# 20260108.net
KiCad netlist of a schematic drawn in EasyEDA Pro
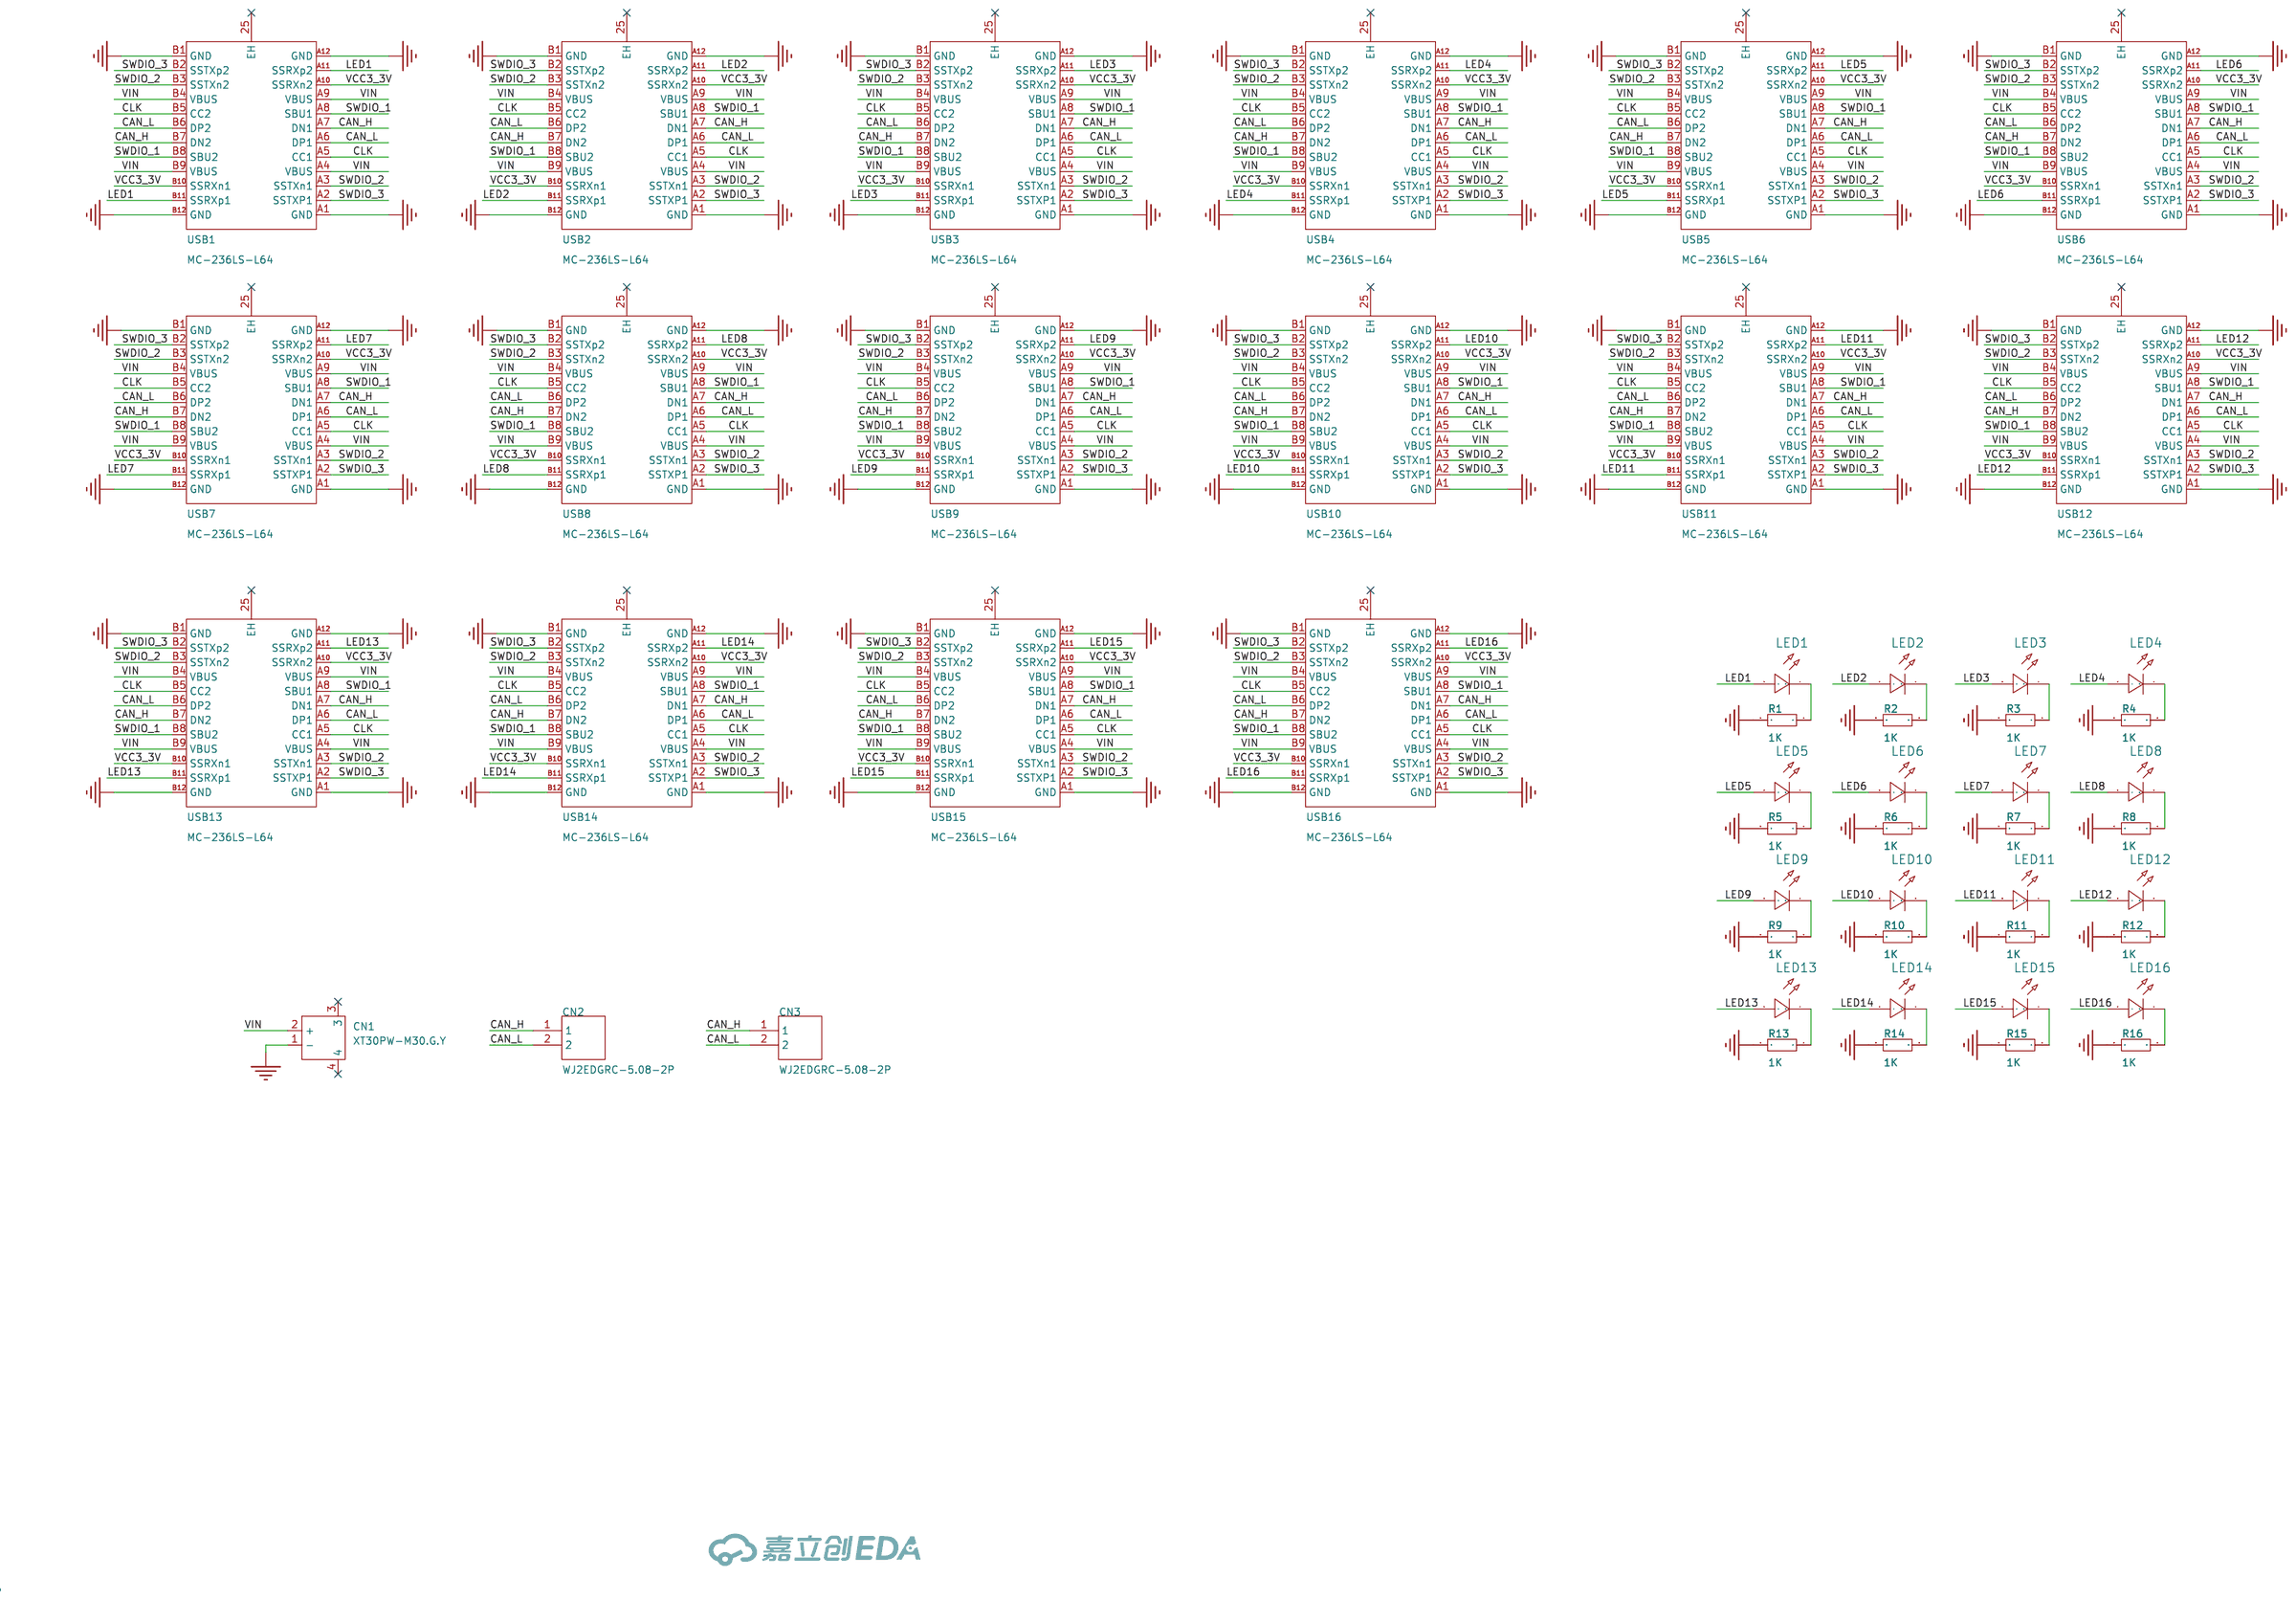
[diagram p0: schematic sheet]

(export (version "E")
  (design (tool "Eeschema 10.0.6"))
  (components
    (comp (ref "CN1")
      (value "XT30PW-M30.G.Y")
      (footprint "easyedapro:CONN-TH_XT30PW-M")
      (description "类别:-;类型1:-;")
      (fields (field (name "Manufacturer") "AMASS(艾迈斯)"))
      (libsource (lib "easyedapro") (part "XT30PW-M"))
    )
    (comp (ref "CN2")
      (value "WJ2EDGRC-5.08-2P")
      (footprint "easyedapro:CONN-TH_2P-P5.08_WJ2EDGRC-5.08-2P")
      (fields (field (name "Manufacturer") "KANGNEX(康奈克斯电气)"))
      (libsource (lib "easyedapro") (part "WJ2EDGRC-5.08-2P"))
    )
    (comp (ref "CN3")
      (value "WJ2EDGRC-5.08-2P")
      (footprint "easyedapro:CONN-TH_2P-P5.08_WJ2EDGRC-5.08-2P")
      (fields (field (name "Manufacturer") "KANGNEX(康奈克斯电气)"))
      (libsource (lib "easyedapro") (part "WJ2EDGRC-5.08-2P"))
    )
    (comp (ref "LED1")
      (value "~")
      (footprint "easyedapro:LED_0805")
      (libsource (lib "easyedapro") (part "LED_R"))
    )
    (comp (ref "LED2")
      (value "~")
      (footprint "easyedapro:LED_0805")
      (libsource (lib "easyedapro") (part "LED_R"))
    )
    (comp (ref "LED3")
      (value "~")
      (footprint "easyedapro:LED_0805")
      (libsource (lib "easyedapro") (part "LED_R"))
    )
    (comp (ref "LED4")
      (value "~")
      (footprint "easyedapro:LED_0805")
      (libsource (lib "easyedapro") (part "LED_R"))
    )
    (comp (ref "LED5")
      (value "~")
      (footprint "easyedapro:LED_0805")
      (libsource (lib "easyedapro") (part "LED_R"))
    )
    (comp (ref "LED6")
      (value "~")
      (footprint "easyedapro:LED_0805")
      (libsource (lib "easyedapro") (part "LED_R"))
    )
    (comp (ref "LED7")
      (value "~")
      (footprint "easyedapro:LED_0805")
      (libsource (lib "easyedapro") (part "LED_R"))
    )
    (comp (ref "LED8")
      (value "~")
      (footprint "easyedapro:LED_0805")
      (libsource (lib "easyedapro") (part "LED_R"))
    )
    (comp (ref "LED9")
      (value "~")
      (footprint "easyedapro:LED_0805")
      (libsource (lib "easyedapro") (part "LED_R"))
    )
    (comp (ref "LED10")
      (value "~")
      (footprint "easyedapro:LED_0805")
      (libsource (lib "easyedapro") (part "LED_R"))
    )
    (comp (ref "LED11")
      (value "~")
      (footprint "easyedapro:LED_0805")
      (libsource (lib "easyedapro") (part "LED_R"))
    )
    (comp (ref "LED12")
      (value "~")
      (footprint "easyedapro:LED_0805")
      (libsource (lib "easyedapro") (part "LED_R"))
    )
    (comp (ref "LED13")
      (value "~")
      (footprint "easyedapro:LED_0805")
      (libsource (lib "easyedapro") (part "LED_R"))
    )
    (comp (ref "LED14")
      (value "~")
      (footprint "easyedapro:LED_0805")
      (libsource (lib "easyedapro") (part "LED_R"))
    )
    (comp (ref "LED15")
      (value "~")
      (footprint "easyedapro:LED_0805")
      (libsource (lib "easyedapro") (part "LED_R"))
    )
    (comp (ref "LED16")
      (value "~")
      (footprint "easyedapro:LED_0805")
      (libsource (lib "easyedapro") (part "LED_R"))
    )
    (comp (ref "R1") (value "1K") (footprint "easyedapro:R0805") (libsource (lib "easyedapro") (part "电阻")))
    (comp (ref "R2") (value "1K") (footprint "easyedapro:R0805") (libsource (lib "easyedapro") (part "电阻")))
    (comp (ref "R3") (value "1K") (footprint "easyedapro:R0805") (libsource (lib "easyedapro") (part "电阻")))
    (comp (ref "R4") (value "1K") (footprint "easyedapro:R0805") (libsource (lib "easyedapro") (part "电阻")))
    (comp (ref "R5") (value "1K") (footprint "easyedapro:R0805") (libsource (lib "easyedapro") (part "电阻")))
    (comp (ref "R6") (value "1K") (footprint "easyedapro:R0805") (libsource (lib "easyedapro") (part "电阻")))
    (comp (ref "R7") (value "1K") (footprint "easyedapro:R0805") (libsource (lib "easyedapro") (part "电阻")))
    (comp (ref "R8") (value "1K") (footprint "easyedapro:R0805") (libsource (lib "easyedapro") (part "电阻")))
    (comp (ref "R9") (value "1K") (footprint "easyedapro:R0805") (libsource (lib "easyedapro") (part "电阻")))
    (comp (ref "R10") (value "1K") (footprint "easyedapro:R0805") (libsource (lib "easyedapro") (part "电阻")))
    (comp (ref "R11") (value "1K") (footprint "easyedapro:R0805") (libsource (lib "easyedapro") (part "电阻")))
    (comp (ref "R12") (value "1K") (footprint "easyedapro:R0805") (libsource (lib "easyedapro") (part "电阻")))
    (comp (ref "R13") (value "1K") (footprint "easyedapro:R0805") (libsource (lib "easyedapro") (part "电阻")))
    (comp (ref "R14") (value "1K") (footprint "easyedapro:R0805") (libsource (lib "easyedapro") (part "电阻")))
    (comp (ref "R15") (value "1K") (footprint "easyedapro:R0805") (libsource (lib "easyedapro") (part "电阻")))
    (comp (ref "R16") (value "1K") (footprint "easyedapro:R0805") (libsource (lib "easyedapro") (part "电阻")))
    (comp (ref "USB1")
      (value "MC-236LS-L64")
      (footprint "easyedapro:TYPE-C-USB-SMD_TYPE-C-31-M-06")
      (description "连接器类型:Type-C;协议标准:USB 3.1;公母:母;安装方式:立贴;触点数量:24P;端口数量:1;额定电流 - 电源:5A;工作温度:-25°C~+85°C;")
      (fields (field (name "Manufacturer") "HANBO(汉博)"))
      (libsource (lib "easyedapro") (part "MC-236LS-L64"))
    )
    (comp (ref "USB2")
      (value "MC-236LS-L64")
      (footprint "easyedapro:TYPE-C-USB-SMD_TYPE-C-31-M-06")
      (description "连接器类型:Type-C;协议标准:USB 3.1;公母:母;安装方式:立贴;触点数量:24P;端口数量:1;额定电流 - 电源:5A;工作温度:-25°C~+85°C;")
      (fields (field (name "Manufacturer") "HANBO(汉博)"))
      (libsource (lib "easyedapro") (part "MC-236LS-L64"))
    )
    (comp (ref "USB3")
      (value "MC-236LS-L64")
      (footprint "easyedapro:TYPE-C-USB-SMD_TYPE-C-31-M-06")
      (description "连接器类型:Type-C;协议标准:USB 3.1;公母:母;安装方式:立贴;触点数量:24P;端口数量:1;额定电流 - 电源:5A;工作温度:-25°C~+85°C;")
      (fields (field (name "Manufacturer") "HANBO(汉博)"))
      (libsource (lib "easyedapro") (part "MC-236LS-L64"))
    )
    (comp (ref "USB4")
      (value "MC-236LS-L64")
      (footprint "easyedapro:TYPE-C-USB-SMD_TYPE-C-31-M-06")
      (description "连接器类型:Type-C;协议标准:USB 3.1;公母:母;安装方式:立贴;触点数量:24P;端口数量:1;额定电流 - 电源:5A;工作温度:-25°C~+85°C;")
      (fields (field (name "Manufacturer") "HANBO(汉博)"))
      (libsource (lib "easyedapro") (part "MC-236LS-L64"))
    )
    (comp (ref "USB5")
      (value "MC-236LS-L64")
      (footprint "easyedapro:TYPE-C-USB-SMD_TYPE-C-31-M-06")
      (description "连接器类型:Type-C;协议标准:USB 3.1;公母:母;安装方式:立贴;触点数量:24P;端口数量:1;额定电流 - 电源:5A;工作温度:-25°C~+85°C;")
      (fields (field (name "Manufacturer") "HANBO(汉博)"))
      (libsource (lib "easyedapro") (part "MC-236LS-L64"))
    )
    (comp (ref "USB6")
      (value "MC-236LS-L64")
      (footprint "easyedapro:TYPE-C-USB-SMD_TYPE-C-31-M-06")
      (description "连接器类型:Type-C;协议标准:USB 3.1;公母:母;安装方式:立贴;触点数量:24P;端口数量:1;额定电流 - 电源:5A;工作温度:-25°C~+85°C;")
      (fields (field (name "Manufacturer") "HANBO(汉博)"))
      (libsource (lib "easyedapro") (part "MC-236LS-L64"))
    )
    (comp (ref "USB7")
      (value "MC-236LS-L64")
      (footprint "easyedapro:TYPE-C-USB-SMD_TYPE-C-31-M-06")
      (description "连接器类型:Type-C;协议标准:USB 3.1;公母:母;安装方式:立贴;触点数量:24P;端口数量:1;额定电流 - 电源:5A;工作温度:-25°C~+85°C;")
      (fields (field (name "Manufacturer") "HANBO(汉博)"))
      (libsource (lib "easyedapro") (part "MC-236LS-L64"))
    )
    (comp (ref "USB8")
      (value "MC-236LS-L64")
      (footprint "easyedapro:TYPE-C-USB-SMD_TYPE-C-31-M-06")
      (description "连接器类型:Type-C;协议标准:USB 3.1;公母:母;安装方式:立贴;触点数量:24P;端口数量:1;额定电流 - 电源:5A;工作温度:-25°C~+85°C;")
      (fields (field (name "Manufacturer") "HANBO(汉博)"))
      (libsource (lib "easyedapro") (part "MC-236LS-L64"))
    )
    (comp (ref "USB9")
      (value "MC-236LS-L64")
      (footprint "easyedapro:TYPE-C-USB-SMD_TYPE-C-31-M-06")
      (description "连接器类型:Type-C;协议标准:USB 3.1;公母:母;安装方式:立贴;触点数量:24P;端口数量:1;额定电流 - 电源:5A;工作温度:-25°C~+85°C;")
      (fields (field (name "Manufacturer") "HANBO(汉博)"))
      (libsource (lib "easyedapro") (part "MC-236LS-L64"))
    )
    (comp (ref "USB10")
      (value "MC-236LS-L64")
      (footprint "easyedapro:TYPE-C-USB-SMD_TYPE-C-31-M-06")
      (description "连接器类型:Type-C;协议标准:USB 3.1;公母:母;安装方式:立贴;触点数量:24P;端口数量:1;额定电流 - 电源:5A;工作温度:-25°C~+85°C;")
      (fields (field (name "Manufacturer") "HANBO(汉博)"))
      (libsource (lib "easyedapro") (part "MC-236LS-L64"))
    )
    (comp (ref "USB11")
      (value "MC-236LS-L64")
      (footprint "easyedapro:TYPE-C-USB-SMD_TYPE-C-31-M-06")
      (description "连接器类型:Type-C;协议标准:USB 3.1;公母:母;安装方式:立贴;触点数量:24P;端口数量:1;额定电流 - 电源:5A;工作温度:-25°C~+85°C;")
      (fields (field (name "Manufacturer") "HANBO(汉博)"))
      (libsource (lib "easyedapro") (part "MC-236LS-L64"))
    )
    (comp (ref "USB12")
      (value "MC-236LS-L64")
      (footprint "easyedapro:TYPE-C-USB-SMD_TYPE-C-31-M-06")
      (description "连接器类型:Type-C;协议标准:USB 3.1;公母:母;安装方式:立贴;触点数量:24P;端口数量:1;额定电流 - 电源:5A;工作温度:-25°C~+85°C;")
      (fields (field (name "Manufacturer") "HANBO(汉博)"))
      (libsource (lib "easyedapro") (part "MC-236LS-L64"))
    )
    (comp (ref "USB13")
      (value "MC-236LS-L64")
      (footprint "easyedapro:TYPE-C-USB-SMD_TYPE-C-31-M-06")
      (description "连接器类型:Type-C;协议标准:USB 3.1;公母:母;安装方式:立贴;触点数量:24P;端口数量:1;额定电流 - 电源:5A;工作温度:-25°C~+85°C;")
      (fields (field (name "Manufacturer") "HANBO(汉博)"))
      (libsource (lib "easyedapro") (part "MC-236LS-L64"))
    )
    (comp (ref "USB14")
      (value "MC-236LS-L64")
      (footprint "easyedapro:TYPE-C-USB-SMD_TYPE-C-31-M-06")
      (description "连接器类型:Type-C;协议标准:USB 3.1;公母:母;安装方式:立贴;触点数量:24P;端口数量:1;额定电流 - 电源:5A;工作温度:-25°C~+85°C;")
      (fields (field (name "Manufacturer") "HANBO(汉博)"))
      (libsource (lib "easyedapro") (part "MC-236LS-L64"))
    )
    (comp (ref "USB15")
      (value "MC-236LS-L64")
      (footprint "easyedapro:TYPE-C-USB-SMD_TYPE-C-31-M-06")
      (description "连接器类型:Type-C;协议标准:USB 3.1;公母:母;安装方式:立贴;触点数量:24P;端口数量:1;额定电流 - 电源:5A;工作温度:-25°C~+85°C;")
      (fields (field (name "Manufacturer") "HANBO(汉博)"))
      (libsource (lib "easyedapro") (part "MC-236LS-L64"))
    )
    (comp (ref "USB16")
      (value "MC-236LS-L64")
      (footprint "easyedapro:TYPE-C-USB-SMD_TYPE-C-31-M-06")
      (description "连接器类型:Type-C;协议标准:USB 3.1;公母:母;安装方式:立贴;触点数量:24P;端口数量:1;额定电流 - 电源:5A;工作温度:-25°C~+85°C;")
      (fields (field (name "Manufacturer") "HANBO(汉博)"))
      (libsource (lib "easyedapro") (part "MC-236LS-L64"))
    )
  )
  (nets
    (net (code "1") (name "/CAN_H") (class "Default")
      (node (ref "CN2") (pin "1") (pinfunction "1_1") (pintype "unspecified"))
      (node (ref "CN3") (pin "1") (pinfunction "1_1") (pintype "unspecified"))
      (node (ref "USB1") (pin "A7") (pinfunction "DN1_A7") (pintype "unspecified"))
      (node (ref "USB1") (pin "B7") (pinfunction "DN2_B7") (pintype "unspecified"))
      (node (ref "USB10") (pin "A7") (pinfunction "DN1_A7") (pintype "unspecified"))
      (node (ref "USB10") (pin "B7") (pinfunction "DN2_B7") (pintype "unspecified"))
      (node (ref "USB11") (pin "A7") (pinfunction "DN1_A7") (pintype "unspecified"))
      (node (ref "USB11") (pin "B7") (pinfunction "DN2_B7") (pintype "unspecified"))
      (node (ref "USB12") (pin "A7") (pinfunction "DN1_A7") (pintype "unspecified"))
      (node (ref "USB12") (pin "B7") (pinfunction "DN2_B7") (pintype "unspecified"))
      (node (ref "USB13") (pin "A7") (pinfunction "DN1_A7") (pintype "unspecified"))
      (node (ref "USB13") (pin "B7") (pinfunction "DN2_B7") (pintype "unspecified"))
      (node (ref "USB14") (pin "A7") (pinfunction "DN1_A7") (pintype "unspecified"))
      (node (ref "USB14") (pin "B7") (pinfunction "DN2_B7") (pintype "unspecified"))
      (node (ref "USB15") (pin "A7") (pinfunction "DN1_A7") (pintype "unspecified"))
      (node (ref "USB15") (pin "B7") (pinfunction "DN2_B7") (pintype "unspecified"))
      (node (ref "USB16") (pin "A7") (pinfunction "DN1_A7") (pintype "unspecified"))
      (node (ref "USB16") (pin "B7") (pinfunction "DN2_B7") (pintype "unspecified"))
      (node (ref "USB2") (pin "A7") (pinfunction "DN1_A7") (pintype "unspecified"))
      (node (ref "USB2") (pin "B7") (pinfunction "DN2_B7") (pintype "unspecified"))
      (node (ref "USB3") (pin "A7") (pinfunction "DN1_A7") (pintype "unspecified"))
      (node (ref "USB3") (pin "B7") (pinfunction "DN2_B7") (pintype "unspecified"))
      (node (ref "USB4") (pin "A7") (pinfunction "DN1_A7") (pintype "unspecified"))
      (node (ref "USB4") (pin "B7") (pinfunction "DN2_B7") (pintype "unspecified"))
      (node (ref "USB5") (pin "A7") (pinfunction "DN1_A7") (pintype "unspecified"))
      (node (ref "USB5") (pin "B7") (pinfunction "DN2_B7") (pintype "unspecified"))
      (node (ref "USB6") (pin "A7") (pinfunction "DN1_A7") (pintype "unspecified"))
      (node (ref "USB6") (pin "B7") (pinfunction "DN2_B7") (pintype "unspecified"))
      (node (ref "USB7") (pin "A7") (pinfunction "DN1_A7") (pintype "unspecified"))
      (node (ref "USB7") (pin "B7") (pinfunction "DN2_B7") (pintype "unspecified"))
      (node (ref "USB8") (pin "A7") (pinfunction "DN1_A7") (pintype "unspecified"))
      (node (ref "USB8") (pin "B7") (pinfunction "DN2_B7") (pintype "unspecified"))
      (node (ref "USB9") (pin "A7") (pinfunction "DN1_A7") (pintype "unspecified"))
      (node (ref "USB9") (pin "B7") (pinfunction "DN2_B7") (pintype "unspecified"))
    )
    (net (code "2") (name "/CAN_L") (class "Default")
      (node (ref "CN2") (pin "2") (pinfunction "2_2") (pintype "unspecified"))
      (node (ref "CN3") (pin "2") (pinfunction "2_2") (pintype "unspecified"))
      (node (ref "USB1") (pin "A6") (pinfunction "DP1_A6") (pintype "unspecified"))
      (node (ref "USB1") (pin "B6") (pinfunction "DP2_B6") (pintype "unspecified"))
      (node (ref "USB10") (pin "A6") (pinfunction "DP1_A6") (pintype "unspecified"))
      (node (ref "USB10") (pin "B6") (pinfunction "DP2_B6") (pintype "unspecified"))
      (node (ref "USB11") (pin "A6") (pinfunction "DP1_A6") (pintype "unspecified"))
      (node (ref "USB11") (pin "B6") (pinfunction "DP2_B6") (pintype "unspecified"))
      (node (ref "USB12") (pin "A6") (pinfunction "DP1_A6") (pintype "unspecified"))
      (node (ref "USB12") (pin "B6") (pinfunction "DP2_B6") (pintype "unspecified"))
      (node (ref "USB13") (pin "A6") (pinfunction "DP1_A6") (pintype "unspecified"))
      (node (ref "USB13") (pin "B6") (pinfunction "DP2_B6") (pintype "unspecified"))
      (node (ref "USB14") (pin "A6") (pinfunction "DP1_A6") (pintype "unspecified"))
      (node (ref "USB14") (pin "B6") (pinfunction "DP2_B6") (pintype "unspecified"))
      (node (ref "USB15") (pin "A6") (pinfunction "DP1_A6") (pintype "unspecified"))
      (node (ref "USB15") (pin "B6") (pinfunction "DP2_B6") (pintype "unspecified"))
      (node (ref "USB16") (pin "A6") (pinfunction "DP1_A6") (pintype "unspecified"))
      (node (ref "USB16") (pin "B6") (pinfunction "DP2_B6") (pintype "unspecified"))
      (node (ref "USB2") (pin "A6") (pinfunction "DP1_A6") (pintype "unspecified"))
      (node (ref "USB2") (pin "B6") (pinfunction "DP2_B6") (pintype "unspecified"))
      (node (ref "USB3") (pin "A6") (pinfunction "DP1_A6") (pintype "unspecified"))
      (node (ref "USB3") (pin "B6") (pinfunction "DP2_B6") (pintype "unspecified"))
      (node (ref "USB4") (pin "A6") (pinfunction "DP1_A6") (pintype "unspecified"))
      (node (ref "USB4") (pin "B6") (pinfunction "DP2_B6") (pintype "unspecified"))
      (node (ref "USB5") (pin "A6") (pinfunction "DP1_A6") (pintype "unspecified"))
      (node (ref "USB5") (pin "B6") (pinfunction "DP2_B6") (pintype "unspecified"))
      (node (ref "USB6") (pin "A6") (pinfunction "DP1_A6") (pintype "unspecified"))
      (node (ref "USB6") (pin "B6") (pinfunction "DP2_B6") (pintype "unspecified"))
      (node (ref "USB7") (pin "A6") (pinfunction "DP1_A6") (pintype "unspecified"))
      (node (ref "USB7") (pin "B6") (pinfunction "DP2_B6") (pintype "unspecified"))
      (node (ref "USB8") (pin "A6") (pinfunction "DP1_A6") (pintype "unspecified"))
      (node (ref "USB8") (pin "B6") (pinfunction "DP2_B6") (pintype "unspecified"))
      (node (ref "USB9") (pin "A6") (pinfunction "DP1_A6") (pintype "unspecified"))
      (node (ref "USB9") (pin "B6") (pinfunction "DP2_B6") (pintype "unspecified"))
    )
    (net (code "3") (name "/CLK") (class "Default")
      (node (ref "USB1") (pin "A5") (pinfunction "CC1_A5") (pintype "unspecified"))
      (node (ref "USB1") (pin "B5") (pinfunction "CC2_B5") (pintype "unspecified"))
      (node (ref "USB10") (pin "A5") (pinfunction "CC1_A5") (pintype "unspecified"))
      (node (ref "USB10") (pin "B5") (pinfunction "CC2_B5") (pintype "unspecified"))
      (node (ref "USB11") (pin "A5") (pinfunction "CC1_A5") (pintype "unspecified"))
      (node (ref "USB11") (pin "B5") (pinfunction "CC2_B5") (pintype "unspecified"))
      (node (ref "USB12") (pin "A5") (pinfunction "CC1_A5") (pintype "unspecified"))
      (node (ref "USB12") (pin "B5") (pinfunction "CC2_B5") (pintype "unspecified"))
      (node (ref "USB13") (pin "A5") (pinfunction "CC1_A5") (pintype "unspecified"))
      (node (ref "USB13") (pin "B5") (pinfunction "CC2_B5") (pintype "unspecified"))
      (node (ref "USB14") (pin "A5") (pinfunction "CC1_A5") (pintype "unspecified"))
      (node (ref "USB14") (pin "B5") (pinfunction "CC2_B5") (pintype "unspecified"))
      (node (ref "USB15") (pin "A5") (pinfunction "CC1_A5") (pintype "unspecified"))
      (node (ref "USB15") (pin "B5") (pinfunction "CC2_B5") (pintype "unspecified"))
      (node (ref "USB16") (pin "A5") (pinfunction "CC1_A5") (pintype "unspecified"))
      (node (ref "USB16") (pin "B5") (pinfunction "CC2_B5") (pintype "unspecified"))
      (node (ref "USB2") (pin "A5") (pinfunction "CC1_A5") (pintype "unspecified"))
      (node (ref "USB2") (pin "B5") (pinfunction "CC2_B5") (pintype "unspecified"))
      (node (ref "USB3") (pin "A5") (pinfunction "CC1_A5") (pintype "unspecified"))
      (node (ref "USB3") (pin "B5") (pinfunction "CC2_B5") (pintype "unspecified"))
      (node (ref "USB4") (pin "A5") (pinfunction "CC1_A5") (pintype "unspecified"))
      (node (ref "USB4") (pin "B5") (pinfunction "CC2_B5") (pintype "unspecified"))
      (node (ref "USB5") (pin "A5") (pinfunction "CC1_A5") (pintype "unspecified"))
      (node (ref "USB5") (pin "B5") (pinfunction "CC2_B5") (pintype "unspecified"))
      (node (ref "USB6") (pin "A5") (pinfunction "CC1_A5") (pintype "unspecified"))
      (node (ref "USB6") (pin "B5") (pinfunction "CC2_B5") (pintype "unspecified"))
      (node (ref "USB7") (pin "A5") (pinfunction "CC1_A5") (pintype "unspecified"))
      (node (ref "USB7") (pin "B5") (pinfunction "CC2_B5") (pintype "unspecified"))
      (node (ref "USB8") (pin "A5") (pinfunction "CC1_A5") (pintype "unspecified"))
      (node (ref "USB8") (pin "B5") (pinfunction "CC2_B5") (pintype "unspecified"))
      (node (ref "USB9") (pin "A5") (pinfunction "CC1_A5") (pintype "unspecified"))
      (node (ref "USB9") (pin "B5") (pinfunction "CC2_B5") (pintype "unspecified"))
    )
    (net (code "4") (name "/LED1") (class "Default")
      (node (ref "LED1") (pin "2") (pinfunction "A_2") (pintype "input"))
      (node (ref "USB1") (pin "A11") (pinfunction "SSRXp2_A11") (pintype "unspecified"))
      (node (ref "USB1") (pin "B11") (pinfunction "SSRXp1_B11") (pintype "unspecified"))
    )
    (net (code "5") (name "/LED2") (class "Default")
      (node (ref "LED2") (pin "2") (pinfunction "A_2") (pintype "input"))
      (node (ref "USB2") (pin "A11") (pinfunction "SSRXp2_A11") (pintype "unspecified"))
      (node (ref "USB2") (pin "B11") (pinfunction "SSRXp1_B11") (pintype "unspecified"))
    )
    (net (code "6") (name "/LED3") (class "Default")
      (node (ref "LED3") (pin "2") (pinfunction "A_2") (pintype "input"))
      (node (ref "USB3") (pin "A11") (pinfunction "SSRXp2_A11") (pintype "unspecified"))
      (node (ref "USB3") (pin "B11") (pinfunction "SSRXp1_B11") (pintype "unspecified"))
    )
    (net (code "7") (name "/LED4") (class "Default")
      (node (ref "LED4") (pin "2") (pinfunction "A_2") (pintype "input"))
      (node (ref "USB4") (pin "A11") (pinfunction "SSRXp2_A11") (pintype "unspecified"))
      (node (ref "USB4") (pin "B11") (pinfunction "SSRXp1_B11") (pintype "unspecified"))
    )
    (net (code "8") (name "/LED5") (class "Default")
      (node (ref "LED5") (pin "2") (pinfunction "A_2") (pintype "input"))
      (node (ref "USB5") (pin "A11") (pinfunction "SSRXp2_A11") (pintype "unspecified"))
      (node (ref "USB5") (pin "B11") (pinfunction "SSRXp1_B11") (pintype "unspecified"))
    )
    (net (code "9") (name "/LED6") (class "Default")
      (node (ref "LED6") (pin "2") (pinfunction "A_2") (pintype "input"))
      (node (ref "USB6") (pin "A11") (pinfunction "SSRXp2_A11") (pintype "unspecified"))
      (node (ref "USB6") (pin "B11") (pinfunction "SSRXp1_B11") (pintype "unspecified"))
    )
    (net (code "10") (name "/LED7") (class "Default")
      (node (ref "LED7") (pin "2") (pinfunction "A_2") (pintype "input"))
      (node (ref "USB7") (pin "A11") (pinfunction "SSRXp2_A11") (pintype "unspecified"))
      (node (ref "USB7") (pin "B11") (pinfunction "SSRXp1_B11") (pintype "unspecified"))
    )
    (net (code "11") (name "/LED8") (class "Default")
      (node (ref "LED8") (pin "2") (pinfunction "A_2") (pintype "input"))
      (node (ref "USB8") (pin "A11") (pinfunction "SSRXp2_A11") (pintype "unspecified"))
      (node (ref "USB8") (pin "B11") (pinfunction "SSRXp1_B11") (pintype "unspecified"))
    )
    (net (code "12") (name "/LED9") (class "Default")
      (node (ref "LED9") (pin "2") (pinfunction "A_2") (pintype "input"))
      (node (ref "USB9") (pin "A11") (pinfunction "SSRXp2_A11") (pintype "unspecified"))
      (node (ref "USB9") (pin "B11") (pinfunction "SSRXp1_B11") (pintype "unspecified"))
    )
    (net (code "13") (name "/LED10") (class "Default")
      (node (ref "LED10") (pin "2") (pinfunction "A_2") (pintype "input"))
      (node (ref "USB10") (pin "A11") (pinfunction "SSRXp2_A11") (pintype "unspecified"))
      (node (ref "USB10") (pin "B11") (pinfunction "SSRXp1_B11") (pintype "unspecified"))
    )
    (net (code "14") (name "/LED11") (class "Default")
      (node (ref "LED11") (pin "2") (pinfunction "A_2") (pintype "input"))
      (node (ref "USB11") (pin "A11") (pinfunction "SSRXp2_A11") (pintype "unspecified"))
      (node (ref "USB11") (pin "B11") (pinfunction "SSRXp1_B11") (pintype "unspecified"))
    )
    (net (code "15") (name "/LED12") (class "Default")
      (node (ref "LED12") (pin "2") (pinfunction "A_2") (pintype "input"))
      (node (ref "USB12") (pin "A11") (pinfunction "SSRXp2_A11") (pintype "unspecified"))
      (node (ref "USB12") (pin "B11") (pinfunction "SSRXp1_B11") (pintype "unspecified"))
    )
    (net (code "16") (name "/LED13") (class "Default")
      (node (ref "LED13") (pin "2") (pinfunction "A_2") (pintype "input"))
      (node (ref "USB13") (pin "A11") (pinfunction "SSRXp2_A11") (pintype "unspecified"))
      (node (ref "USB13") (pin "B11") (pinfunction "SSRXp1_B11") (pintype "unspecified"))
    )
    (net (code "17") (name "/LED14") (class "Default")
      (node (ref "LED14") (pin "2") (pinfunction "A_2") (pintype "input"))
      (node (ref "USB14") (pin "A11") (pinfunction "SSRXp2_A11") (pintype "unspecified"))
      (node (ref "USB14") (pin "B11") (pinfunction "SSRXp1_B11") (pintype "unspecified"))
    )
    (net (code "18") (name "/LED15") (class "Default")
      (node (ref "LED15") (pin "2") (pinfunction "A_2") (pintype "input"))
      (node (ref "USB15") (pin "A11") (pinfunction "SSRXp2_A11") (pintype "unspecified"))
      (node (ref "USB15") (pin "B11") (pinfunction "SSRXp1_B11") (pintype "unspecified"))
    )
    (net (code "19") (name "/LED16") (class "Default")
      (node (ref "LED16") (pin "2") (pinfunction "A_2") (pintype "input"))
      (node (ref "USB16") (pin "A11") (pinfunction "SSRXp2_A11") (pintype "unspecified"))
      (node (ref "USB16") (pin "B11") (pinfunction "SSRXp1_B11") (pintype "unspecified"))
    )
    (net (code "20") (name "/SWDIO_1") (class "Default")
      (node (ref "USB1") (pin "A8") (pinfunction "SBU1_A8") (pintype "unspecified"))
      (node (ref "USB1") (pin "B8") (pinfunction "SBU2_B8") (pintype "unspecified"))
      (node (ref "USB10") (pin "A8") (pinfunction "SBU1_A8") (pintype "unspecified"))
      (node (ref "USB10") (pin "B8") (pinfunction "SBU2_B8") (pintype "unspecified"))
      (node (ref "USB11") (pin "A8") (pinfunction "SBU1_A8") (pintype "unspecified"))
      (node (ref "USB11") (pin "B8") (pinfunction "SBU2_B8") (pintype "unspecified"))
      (node (ref "USB12") (pin "A8") (pinfunction "SBU1_A8") (pintype "unspecified"))
      (node (ref "USB12") (pin "B8") (pinfunction "SBU2_B8") (pintype "unspecified"))
      (node (ref "USB13") (pin "A8") (pinfunction "SBU1_A8") (pintype "unspecified"))
      (node (ref "USB13") (pin "B8") (pinfunction "SBU2_B8") (pintype "unspecified"))
      (node (ref "USB14") (pin "A8") (pinfunction "SBU1_A8") (pintype "unspecified"))
      (node (ref "USB14") (pin "B8") (pinfunction "SBU2_B8") (pintype "unspecified"))
      (node (ref "USB15") (pin "A8") (pinfunction "SBU1_A8") (pintype "unspecified"))
      (node (ref "USB15") (pin "B8") (pinfunction "SBU2_B8") (pintype "unspecified"))
      (node (ref "USB16") (pin "A8") (pinfunction "SBU1_A8") (pintype "unspecified"))
      (node (ref "USB16") (pin "B8") (pinfunction "SBU2_B8") (pintype "unspecified"))
      (node (ref "USB2") (pin "A8") (pinfunction "SBU1_A8") (pintype "unspecified"))
      (node (ref "USB2") (pin "B8") (pinfunction "SBU2_B8") (pintype "unspecified"))
      (node (ref "USB3") (pin "A8") (pinfunction "SBU1_A8") (pintype "unspecified"))
      (node (ref "USB3") (pin "B8") (pinfunction "SBU2_B8") (pintype "unspecified"))
      (node (ref "USB4") (pin "A8") (pinfunction "SBU1_A8") (pintype "unspecified"))
      (node (ref "USB4") (pin "B8") (pinfunction "SBU2_B8") (pintype "unspecified"))
      (node (ref "USB5") (pin "A8") (pinfunction "SBU1_A8") (pintype "unspecified"))
      (node (ref "USB5") (pin "B8") (pinfunction "SBU2_B8") (pintype "unspecified"))
      (node (ref "USB6") (pin "A8") (pinfunction "SBU1_A8") (pintype "unspecified"))
      (node (ref "USB6") (pin "B8") (pinfunction "SBU2_B8") (pintype "unspecified"))
      (node (ref "USB7") (pin "A8") (pinfunction "SBU1_A8") (pintype "unspecified"))
      (node (ref "USB7") (pin "B8") (pinfunction "SBU2_B8") (pintype "unspecified"))
      (node (ref "USB8") (pin "A8") (pinfunction "SBU1_A8") (pintype "unspecified"))
      (node (ref "USB8") (pin "B8") (pinfunction "SBU2_B8") (pintype "unspecified"))
      (node (ref "USB9") (pin "A8") (pinfunction "SBU1_A8") (pintype "unspecified"))
      (node (ref "USB9") (pin "B8") (pinfunction "SBU2_B8") (pintype "unspecified"))
    )
    (net (code "21") (name "/SWDIO_2") (class "Default")
      (node (ref "USB1") (pin "A3") (pinfunction "SSTXn1_A3") (pintype "unspecified"))
      (node (ref "USB1") (pin "B3") (pinfunction "SSTXn2_B3") (pintype "unspecified"))
      (node (ref "USB10") (pin "A3") (pinfunction "SSTXn1_A3") (pintype "unspecified"))
      (node (ref "USB10") (pin "B3") (pinfunction "SSTXn2_B3") (pintype "unspecified"))
      (node (ref "USB11") (pin "A3") (pinfunction "SSTXn1_A3") (pintype "unspecified"))
      (node (ref "USB11") (pin "B3") (pinfunction "SSTXn2_B3") (pintype "unspecified"))
      (node (ref "USB12") (pin "A3") (pinfunction "SSTXn1_A3") (pintype "unspecified"))
      (node (ref "USB12") (pin "B3") (pinfunction "SSTXn2_B3") (pintype "unspecified"))
      (node (ref "USB13") (pin "A3") (pinfunction "SSTXn1_A3") (pintype "unspecified"))
      (node (ref "USB13") (pin "B3") (pinfunction "SSTXn2_B3") (pintype "unspecified"))
      (node (ref "USB14") (pin "A3") (pinfunction "SSTXn1_A3") (pintype "unspecified"))
      (node (ref "USB14") (pin "B3") (pinfunction "SSTXn2_B3") (pintype "unspecified"))
      (node (ref "USB15") (pin "A3") (pinfunction "SSTXn1_A3") (pintype "unspecified"))
      (node (ref "USB15") (pin "B3") (pinfunction "SSTXn2_B3") (pintype "unspecified"))
      (node (ref "USB16") (pin "A3") (pinfunction "SSTXn1_A3") (pintype "unspecified"))
      (node (ref "USB16") (pin "B3") (pinfunction "SSTXn2_B3") (pintype "unspecified"))
      (node (ref "USB2") (pin "A3") (pinfunction "SSTXn1_A3") (pintype "unspecified"))
      (node (ref "USB2") (pin "B3") (pinfunction "SSTXn2_B3") (pintype "unspecified"))
      (node (ref "USB3") (pin "A3") (pinfunction "SSTXn1_A3") (pintype "unspecified"))
      (node (ref "USB3") (pin "B3") (pinfunction "SSTXn2_B3") (pintype "unspecified"))
      (node (ref "USB4") (pin "A3") (pinfunction "SSTXn1_A3") (pintype "unspecified"))
      (node (ref "USB4") (pin "B3") (pinfunction "SSTXn2_B3") (pintype "unspecified"))
      (node (ref "USB5") (pin "A3") (pinfunction "SSTXn1_A3") (pintype "unspecified"))
      (node (ref "USB5") (pin "B3") (pinfunction "SSTXn2_B3") (pintype "unspecified"))
      (node (ref "USB6") (pin "A3") (pinfunction "SSTXn1_A3") (pintype "unspecified"))
      (node (ref "USB6") (pin "B3") (pinfunction "SSTXn2_B3") (pintype "unspecified"))
      (node (ref "USB7") (pin "A3") (pinfunction "SSTXn1_A3") (pintype "unspecified"))
      (node (ref "USB7") (pin "B3") (pinfunction "SSTXn2_B3") (pintype "unspecified"))
      (node (ref "USB8") (pin "A3") (pinfunction "SSTXn1_A3") (pintype "unspecified"))
      (node (ref "USB8") (pin "B3") (pinfunction "SSTXn2_B3") (pintype "unspecified"))
      (node (ref "USB9") (pin "A3") (pinfunction "SSTXn1_A3") (pintype "unspecified"))
      (node (ref "USB9") (pin "B3") (pinfunction "SSTXn2_B3") (pintype "unspecified"))
    )
    (net (code "22") (name "/SWDIO_3") (class "Default")
      (node (ref "USB1") (pin "A2") (pinfunction "SSTXP1_A2") (pintype "unspecified"))
      (node (ref "USB1") (pin "B2") (pinfunction "SSTXp2_B2") (pintype "unspecified"))
      (node (ref "USB10") (pin "A2") (pinfunction "SSTXP1_A2") (pintype "unspecified"))
      (node (ref "USB10") (pin "B2") (pinfunction "SSTXp2_B2") (pintype "unspecified"))
      (node (ref "USB11") (pin "A2") (pinfunction "SSTXP1_A2") (pintype "unspecified"))
      (node (ref "USB11") (pin "B2") (pinfunction "SSTXp2_B2") (pintype "unspecified"))
      (node (ref "USB12") (pin "A2") (pinfunction "SSTXP1_A2") (pintype "unspecified"))
      (node (ref "USB12") (pin "B2") (pinfunction "SSTXp2_B2") (pintype "unspecified"))
      (node (ref "USB13") (pin "A2") (pinfunction "SSTXP1_A2") (pintype "unspecified"))
      (node (ref "USB13") (pin "B2") (pinfunction "SSTXp2_B2") (pintype "unspecified"))
      (node (ref "USB14") (pin "A2") (pinfunction "SSTXP1_A2") (pintype "unspecified"))
      (node (ref "USB14") (pin "B2") (pinfunction "SSTXp2_B2") (pintype "unspecified"))
      (node (ref "USB15") (pin "A2") (pinfunction "SSTXP1_A2") (pintype "unspecified"))
      (node (ref "USB15") (pin "B2") (pinfunction "SSTXp2_B2") (pintype "unspecified"))
      (node (ref "USB16") (pin "A2") (pinfunction "SSTXP1_A2") (pintype "unspecified"))
      (node (ref "USB16") (pin "B2") (pinfunction "SSTXp2_B2") (pintype "unspecified"))
      (node (ref "USB2") (pin "A2") (pinfunction "SSTXP1_A2") (pintype "unspecified"))
      (node (ref "USB2") (pin "B2") (pinfunction "SSTXp2_B2") (pintype "unspecified"))
      (node (ref "USB3") (pin "A2") (pinfunction "SSTXP1_A2") (pintype "unspecified"))
      (node (ref "USB3") (pin "B2") (pinfunction "SSTXp2_B2") (pintype "unspecified"))
      (node (ref "USB4") (pin "A2") (pinfunction "SSTXP1_A2") (pintype "unspecified"))
      (node (ref "USB4") (pin "B2") (pinfunction "SSTXp2_B2") (pintype "unspecified"))
      (node (ref "USB5") (pin "A2") (pinfunction "SSTXP1_A2") (pintype "unspecified"))
      (node (ref "USB5") (pin "B2") (pinfunction "SSTXp2_B2") (pintype "unspecified"))
      (node (ref "USB6") (pin "A2") (pinfunction "SSTXP1_A2") (pintype "unspecified"))
      (node (ref "USB6") (pin "B2") (pinfunction "SSTXp2_B2") (pintype "unspecified"))
      (node (ref "USB7") (pin "A2") (pinfunction "SSTXP1_A2") (pintype "unspecified"))
      (node (ref "USB7") (pin "B2") (pinfunction "SSTXp2_B2") (pintype "unspecified"))
      (node (ref "USB8") (pin "A2") (pinfunction "SSTXP1_A2") (pintype "unspecified"))
      (node (ref "USB8") (pin "B2") (pinfunction "SSTXp2_B2") (pintype "unspecified"))
      (node (ref "USB9") (pin "A2") (pinfunction "SSTXP1_A2") (pintype "unspecified"))
      (node (ref "USB9") (pin "B2") (pinfunction "SSTXp2_B2") (pintype "unspecified"))
    )
    (net (code "23") (name "/VCC3_3V") (class "Default")
      (node (ref "USB1") (pin "A10") (pinfunction "SSRXn2_A10") (pintype "unspecified"))
      (node (ref "USB1") (pin "B10") (pinfunction "SSRXn1_B10") (pintype "unspecified"))
      (node (ref "USB10") (pin "A10") (pinfunction "SSRXn2_A10") (pintype "unspecified"))
      (node (ref "USB10") (pin "B10") (pinfunction "SSRXn1_B10") (pintype "unspecified"))
      (node (ref "USB11") (pin "A10") (pinfunction "SSRXn2_A10") (pintype "unspecified"))
      (node (ref "USB11") (pin "B10") (pinfunction "SSRXn1_B10") (pintype "unspecified"))
      (node (ref "USB12") (pin "A10") (pinfunction "SSRXn2_A10") (pintype "unspecified"))
      (node (ref "USB12") (pin "B10") (pinfunction "SSRXn1_B10") (pintype "unspecified"))
      (node (ref "USB13") (pin "A10") (pinfunction "SSRXn2_A10") (pintype "unspecified"))
      (node (ref "USB13") (pin "B10") (pinfunction "SSRXn1_B10") (pintype "unspecified"))
      (node (ref "USB14") (pin "A10") (pinfunction "SSRXn2_A10") (pintype "unspecified"))
      (node (ref "USB14") (pin "B10") (pinfunction "SSRXn1_B10") (pintype "unspecified"))
      (node (ref "USB15") (pin "A10") (pinfunction "SSRXn2_A10") (pintype "unspecified"))
      (node (ref "USB15") (pin "B10") (pinfunction "SSRXn1_B10") (pintype "unspecified"))
      (node (ref "USB16") (pin "A10") (pinfunction "SSRXn2_A10") (pintype "unspecified"))
      (node (ref "USB16") (pin "B10") (pinfunction "SSRXn1_B10") (pintype "unspecified"))
      (node (ref "USB2") (pin "A10") (pinfunction "SSRXn2_A10") (pintype "unspecified"))
      (node (ref "USB2") (pin "B10") (pinfunction "SSRXn1_B10") (pintype "unspecified"))
      (node (ref "USB3") (pin "A10") (pinfunction "SSRXn2_A10") (pintype "unspecified"))
      (node (ref "USB3") (pin "B10") (pinfunction "SSRXn1_B10") (pintype "unspecified"))
      (node (ref "USB4") (pin "A10") (pinfunction "SSRXn2_A10") (pintype "unspecified"))
      (node (ref "USB4") (pin "B10") (pinfunction "SSRXn1_B10") (pintype "unspecified"))
      (node (ref "USB5") (pin "A10") (pinfunction "SSRXn2_A10") (pintype "unspecified"))
      (node (ref "USB5") (pin "B10") (pinfunction "SSRXn1_B10") (pintype "unspecified"))
      (node (ref "USB6") (pin "A10") (pinfunction "SSRXn2_A10") (pintype "unspecified"))
      (node (ref "USB6") (pin "B10") (pinfunction "SSRXn1_B10") (pintype "unspecified"))
      (node (ref "USB7") (pin "A10") (pinfunction "SSRXn2_A10") (pintype "unspecified"))
      (node (ref "USB7") (pin "B10") (pinfunction "SSRXn1_B10") (pintype "unspecified"))
      (node (ref "USB8") (pin "A10") (pinfunction "SSRXn2_A10") (pintype "unspecified"))
      (node (ref "USB8") (pin "B10") (pinfunction "SSRXn1_B10") (pintype "unspecified"))
      (node (ref "USB9") (pin "A10") (pinfunction "SSRXn2_A10") (pintype "unspecified"))
      (node (ref "USB9") (pin "B10") (pinfunction "SSRXn1_B10") (pintype "unspecified"))
    )
    (net (code "24") (name "/VIN") (class "Default")
      (node (ref "CN1") (pin "2") (pinfunction "+_2") (pintype "unspecified"))
      (node (ref "USB1") (pin "A4") (pinfunction "VBUS_A4") (pintype "unspecified"))
      (node (ref "USB1") (pin "A9") (pinfunction "VBUS_A9") (pintype "unspecified"))
      (node (ref "USB1") (pin "B4") (pinfunction "VBUS_B4") (pintype "unspecified"))
      (node (ref "USB1") (pin "B9") (pinfunction "VBUS_B9") (pintype "unspecified"))
      (node (ref "USB10") (pin "A4") (pinfunction "VBUS_A4") (pintype "unspecified"))
      (node (ref "USB10") (pin "A9") (pinfunction "VBUS_A9") (pintype "unspecified"))
      (node (ref "USB10") (pin "B4") (pinfunction "VBUS_B4") (pintype "unspecified"))
      (node (ref "USB10") (pin "B9") (pinfunction "VBUS_B9") (pintype "unspecified"))
      (node (ref "USB11") (pin "A4") (pinfunction "VBUS_A4") (pintype "unspecified"))
      (node (ref "USB11") (pin "A9") (pinfunction "VBUS_A9") (pintype "unspecified"))
      (node (ref "USB11") (pin "B4") (pinfunction "VBUS_B4") (pintype "unspecified"))
      (node (ref "USB11") (pin "B9") (pinfunction "VBUS_B9") (pintype "unspecified"))
      (node (ref "USB12") (pin "A4") (pinfunction "VBUS_A4") (pintype "unspecified"))
      (node (ref "USB12") (pin "A9") (pinfunction "VBUS_A9") (pintype "unspecified"))
      (node (ref "USB12") (pin "B4") (pinfunction "VBUS_B4") (pintype "unspecified"))
      (node (ref "USB12") (pin "B9") (pinfunction "VBUS_B9") (pintype "unspecified"))
      (node (ref "USB13") (pin "A4") (pinfunction "VBUS_A4") (pintype "unspecified"))
      (node (ref "USB13") (pin "A9") (pinfunction "VBUS_A9") (pintype "unspecified"))
      (node (ref "USB13") (pin "B4") (pinfunction "VBUS_B4") (pintype "unspecified"))
      (node (ref "USB13") (pin "B9") (pinfunction "VBUS_B9") (pintype "unspecified"))
      (node (ref "USB14") (pin "A4") (pinfunction "VBUS_A4") (pintype "unspecified"))
      (node (ref "USB14") (pin "A9") (pinfunction "VBUS_A9") (pintype "unspecified"))
      (node (ref "USB14") (pin "B4") (pinfunction "VBUS_B4") (pintype "unspecified"))
      (node (ref "USB14") (pin "B9") (pinfunction "VBUS_B9") (pintype "unspecified"))
      (node (ref "USB15") (pin "A4") (pinfunction "VBUS_A4") (pintype "unspecified"))
      (node (ref "USB15") (pin "A9") (pinfunction "VBUS_A9") (pintype "unspecified"))
      (node (ref "USB15") (pin "B4") (pinfunction "VBUS_B4") (pintype "unspecified"))
      (node (ref "USB15") (pin "B9") (pinfunction "VBUS_B9") (pintype "unspecified"))
      (node (ref "USB16") (pin "A4") (pinfunction "VBUS_A4") (pintype "unspecified"))
      (node (ref "USB16") (pin "A9") (pinfunction "VBUS_A9") (pintype "unspecified"))
      (node (ref "USB16") (pin "B4") (pinfunction "VBUS_B4") (pintype "unspecified"))
      (node (ref "USB16") (pin "B9") (pinfunction "VBUS_B9") (pintype "unspecified"))
      (node (ref "USB2") (pin "A4") (pinfunction "VBUS_A4") (pintype "unspecified"))
      (node (ref "USB2") (pin "A9") (pinfunction "VBUS_A9") (pintype "unspecified"))
      (node (ref "USB2") (pin "B4") (pinfunction "VBUS_B4") (pintype "unspecified"))
      (node (ref "USB2") (pin "B9") (pinfunction "VBUS_B9") (pintype "unspecified"))
      (node (ref "USB3") (pin "A4") (pinfunction "VBUS_A4") (pintype "unspecified"))
      (node (ref "USB3") (pin "A9") (pinfunction "VBUS_A9") (pintype "unspecified"))
      (node (ref "USB3") (pin "B4") (pinfunction "VBUS_B4") (pintype "unspecified"))
      (node (ref "USB3") (pin "B9") (pinfunction "VBUS_B9") (pintype "unspecified"))
      (node (ref "USB4") (pin "A4") (pinfunction "VBUS_A4") (pintype "unspecified"))
      (node (ref "USB4") (pin "A9") (pinfunction "VBUS_A9") (pintype "unspecified"))
      (node (ref "USB4") (pin "B4") (pinfunction "VBUS_B4") (pintype "unspecified"))
      (node (ref "USB4") (pin "B9") (pinfunction "VBUS_B9") (pintype "unspecified"))
      (node (ref "USB5") (pin "A4") (pinfunction "VBUS_A4") (pintype "unspecified"))
      (node (ref "USB5") (pin "A9") (pinfunction "VBUS_A9") (pintype "unspecified"))
      (node (ref "USB5") (pin "B4") (pinfunction "VBUS_B4") (pintype "unspecified"))
      (node (ref "USB5") (pin "B9") (pinfunction "VBUS_B9") (pintype "unspecified"))
      (node (ref "USB6") (pin "A4") (pinfunction "VBUS_A4") (pintype "unspecified"))
      (node (ref "USB6") (pin "A9") (pinfunction "VBUS_A9") (pintype "unspecified"))
      (node (ref "USB6") (pin "B4") (pinfunction "VBUS_B4") (pintype "unspecified"))
      (node (ref "USB6") (pin "B9") (pinfunction "VBUS_B9") (pintype "unspecified"))
      (node (ref "USB7") (pin "A4") (pinfunction "VBUS_A4") (pintype "unspecified"))
      (node (ref "USB7") (pin "A9") (pinfunction "VBUS_A9") (pintype "unspecified"))
      (node (ref "USB7") (pin "B4") (pinfunction "VBUS_B4") (pintype "unspecified"))
      (node (ref "USB7") (pin "B9") (pinfunction "VBUS_B9") (pintype "unspecified"))
      (node (ref "USB8") (pin "A4") (pinfunction "VBUS_A4") (pintype "unspecified"))
      (node (ref "USB8") (pin "A9") (pinfunction "VBUS_A9") (pintype "unspecified"))
      (node (ref "USB8") (pin "B4") (pinfunction "VBUS_B4") (pintype "unspecified"))
      (node (ref "USB8") (pin "B9") (pinfunction "VBUS_B9") (pintype "unspecified"))
      (node (ref "USB9") (pin "A4") (pinfunction "VBUS_A4") (pintype "unspecified"))
      (node (ref "USB9") (pin "A9") (pinfunction "VBUS_A9") (pintype "unspecified"))
      (node (ref "USB9") (pin "B4") (pinfunction "VBUS_B4") (pintype "unspecified"))
      (node (ref "USB9") (pin "B9") (pinfunction "VBUS_B9") (pintype "unspecified"))
    )
    (net (code "25") (name "GND") (class "Default")
      (node (ref "CN1") (pin "1") (pinfunction "-_1") (pintype "unspecified"))
      (node (ref "R1") (pin "2") (pinfunction "2_2") (pintype "input"))
      (node (ref "R10") (pin "2") (pinfunction "2_2") (pintype "input"))
      (node (ref "R11") (pin "2") (pinfunction "2_2") (pintype "input"))
      (node (ref "R12") (pin "2") (pinfunction "2_2") (pintype "input"))
      (node (ref "R13") (pin "2") (pinfunction "2_2") (pintype "input"))
      (node (ref "R14") (pin "2") (pinfunction "2_2") (pintype "input"))
      (node (ref "R15") (pin "2") (pinfunction "2_2") (pintype "input"))
      (node (ref "R16") (pin "2") (pinfunction "2_2") (pintype "input"))
      (node (ref "R2") (pin "2") (pinfunction "2_2") (pintype "input"))
      (node (ref "R3") (pin "2") (pinfunction "2_2") (pintype "input"))
      (node (ref "R4") (pin "2") (pinfunction "2_2") (pintype "input"))
      (node (ref "R5") (pin "2") (pinfunction "2_2") (pintype "input"))
      (node (ref "R6") (pin "2") (pinfunction "2_2") (pintype "input"))
      (node (ref "R7") (pin "2") (pinfunction "2_2") (pintype "input"))
      (node (ref "R8") (pin "2") (pinfunction "2_2") (pintype "input"))
      (node (ref "R9") (pin "2") (pinfunction "2_2") (pintype "input"))
      (node (ref "USB1") (pin "A1") (pinfunction "GND_A1") (pintype "unspecified"))
      (node (ref "USB1") (pin "A12") (pinfunction "GND_A12") (pintype "unspecified"))
      (node (ref "USB1") (pin "B1") (pinfunction "GND_B1") (pintype "unspecified"))
      (node (ref "USB1") (pin "B12") (pinfunction "GND_B12") (pintype "unspecified"))
      (node (ref "USB10") (pin "A1") (pinfunction "GND_A1") (pintype "unspecified"))
      (node (ref "USB10") (pin "A12") (pinfunction "GND_A12") (pintype "unspecified"))
      (node (ref "USB10") (pin "B1") (pinfunction "GND_B1") (pintype "unspecified"))
      (node (ref "USB10") (pin "B12") (pinfunction "GND_B12") (pintype "unspecified"))
      (node (ref "USB11") (pin "A1") (pinfunction "GND_A1") (pintype "unspecified"))
      (node (ref "USB11") (pin "A12") (pinfunction "GND_A12") (pintype "unspecified"))
      (node (ref "USB11") (pin "B1") (pinfunction "GND_B1") (pintype "unspecified"))
      (node (ref "USB11") (pin "B12") (pinfunction "GND_B12") (pintype "unspecified"))
      (node (ref "USB12") (pin "A1") (pinfunction "GND_A1") (pintype "unspecified"))
      (node (ref "USB12") (pin "A12") (pinfunction "GND_A12") (pintype "unspecified"))
      (node (ref "USB12") (pin "B1") (pinfunction "GND_B1") (pintype "unspecified"))
      (node (ref "USB12") (pin "B12") (pinfunction "GND_B12") (pintype "unspecified"))
      (node (ref "USB13") (pin "A1") (pinfunction "GND_A1") (pintype "unspecified"))
      (node (ref "USB13") (pin "A12") (pinfunction "GND_A12") (pintype "unspecified"))
      (node (ref "USB13") (pin "B1") (pinfunction "GND_B1") (pintype "unspecified"))
      (node (ref "USB13") (pin "B12") (pinfunction "GND_B12") (pintype "unspecified"))
      (node (ref "USB14") (pin "A1") (pinfunction "GND_A1") (pintype "unspecified"))
      (node (ref "USB14") (pin "A12") (pinfunction "GND_A12") (pintype "unspecified"))
      (node (ref "USB14") (pin "B1") (pinfunction "GND_B1") (pintype "unspecified"))
      (node (ref "USB14") (pin "B12") (pinfunction "GND_B12") (pintype "unspecified"))
      (node (ref "USB15") (pin "A1") (pinfunction "GND_A1") (pintype "unspecified"))
      (node (ref "USB15") (pin "A12") (pinfunction "GND_A12") (pintype "unspecified"))
      (node (ref "USB15") (pin "B1") (pinfunction "GND_B1") (pintype "unspecified"))
      (node (ref "USB15") (pin "B12") (pinfunction "GND_B12") (pintype "unspecified"))
      (node (ref "USB16") (pin "A1") (pinfunction "GND_A1") (pintype "unspecified"))
      (node (ref "USB16") (pin "A12") (pinfunction "GND_A12") (pintype "unspecified"))
      (node (ref "USB16") (pin "B1") (pinfunction "GND_B1") (pintype "unspecified"))
      (node (ref "USB16") (pin "B12") (pinfunction "GND_B12") (pintype "unspecified"))
      (node (ref "USB2") (pin "A1") (pinfunction "GND_A1") (pintype "unspecified"))
      (node (ref "USB2") (pin "A12") (pinfunction "GND_A12") (pintype "unspecified"))
      (node (ref "USB2") (pin "B1") (pinfunction "GND_B1") (pintype "unspecified"))
      (node (ref "USB2") (pin "B12") (pinfunction "GND_B12") (pintype "unspecified"))
      (node (ref "USB3") (pin "A1") (pinfunction "GND_A1") (pintype "unspecified"))
      (node (ref "USB3") (pin "A12") (pinfunction "GND_A12") (pintype "unspecified"))
      (node (ref "USB3") (pin "B1") (pinfunction "GND_B1") (pintype "unspecified"))
      (node (ref "USB3") (pin "B12") (pinfunction "GND_B12") (pintype "unspecified"))
      (node (ref "USB4") (pin "A1") (pinfunction "GND_A1") (pintype "unspecified"))
      (node (ref "USB4") (pin "A12") (pinfunction "GND_A12") (pintype "unspecified"))
      (node (ref "USB4") (pin "B1") (pinfunction "GND_B1") (pintype "unspecified"))
      (node (ref "USB4") (pin "B12") (pinfunction "GND_B12") (pintype "unspecified"))
      (node (ref "USB5") (pin "A1") (pinfunction "GND_A1") (pintype "unspecified"))
      (node (ref "USB5") (pin "A12") (pinfunction "GND_A12") (pintype "unspecified"))
      (node (ref "USB5") (pin "B1") (pinfunction "GND_B1") (pintype "unspecified"))
      (node (ref "USB5") (pin "B12") (pinfunction "GND_B12") (pintype "unspecified"))
      (node (ref "USB6") (pin "A1") (pinfunction "GND_A1") (pintype "unspecified"))
      (node (ref "USB6") (pin "A12") (pinfunction "GND_A12") (pintype "unspecified"))
      (node (ref "USB6") (pin "B1") (pinfunction "GND_B1") (pintype "unspecified"))
      (node (ref "USB6") (pin "B12") (pinfunction "GND_B12") (pintype "unspecified"))
      (node (ref "USB7") (pin "A1") (pinfunction "GND_A1") (pintype "unspecified"))
      (node (ref "USB7") (pin "A12") (pinfunction "GND_A12") (pintype "unspecified"))
      (node (ref "USB7") (pin "B1") (pinfunction "GND_B1") (pintype "unspecified"))
      (node (ref "USB7") (pin "B12") (pinfunction "GND_B12") (pintype "unspecified"))
      (node (ref "USB8") (pin "A1") (pinfunction "GND_A1") (pintype "unspecified"))
      (node (ref "USB8") (pin "A12") (pinfunction "GND_A12") (pintype "unspecified"))
      (node (ref "USB8") (pin "B1") (pinfunction "GND_B1") (pintype "unspecified"))
      (node (ref "USB8") (pin "B12") (pinfunction "GND_B12") (pintype "unspecified"))
      (node (ref "USB9") (pin "A1") (pinfunction "GND_A1") (pintype "unspecified"))
      (node (ref "USB9") (pin "A12") (pinfunction "GND_A12") (pintype "unspecified"))
      (node (ref "USB9") (pin "B1") (pinfunction "GND_B1") (pintype "unspecified"))
      (node (ref "USB9") (pin "B12") (pinfunction "GND_B12") (pintype "unspecified"))
    )
    (net (code "26") (name "Net-(LED1-C)") (class "Default")
      (node (ref "LED1") (pin "1") (pinfunction "C_1") (pintype "input"))
      (node (ref "R1") (pin "1") (pinfunction "1_1") (pintype "input"))
    )
    (net (code "27") (name "Net-(LED2-C)") (class "Default")
      (node (ref "LED2") (pin "1") (pinfunction "C_1") (pintype "input"))
      (node (ref "R2") (pin "1") (pinfunction "1_1") (pintype "input"))
    )
    (net (code "28") (name "Net-(LED3-C)") (class "Default")
      (node (ref "LED3") (pin "1") (pinfunction "C_1") (pintype "input"))
      (node (ref "R3") (pin "1") (pinfunction "1_1") (pintype "input"))
    )
    (net (code "29") (name "Net-(LED4-C)") (class "Default")
      (node (ref "LED4") (pin "1") (pinfunction "C_1") (pintype "input"))
      (node (ref "R4") (pin "1") (pinfunction "1_1") (pintype "input"))
    )
    (net (code "30") (name "Net-(LED5-C)") (class "Default")
      (node (ref "LED5") (pin "1") (pinfunction "C_1") (pintype "input"))
      (node (ref "R5") (pin "1") (pinfunction "1_1") (pintype "input"))
    )
    (net (code "31") (name "Net-(LED6-C)") (class "Default")
      (node (ref "LED6") (pin "1") (pinfunction "C_1") (pintype "input"))
      (node (ref "R6") (pin "1") (pinfunction "1_1") (pintype "input"))
    )
    (net (code "32") (name "Net-(LED7-C)") (class "Default")
      (node (ref "LED7") (pin "1") (pinfunction "C_1") (pintype "input"))
      (node (ref "R7") (pin "1") (pinfunction "1_1") (pintype "input"))
    )
    (net (code "33") (name "Net-(LED8-C)") (class "Default")
      (node (ref "LED8") (pin "1") (pinfunction "C_1") (pintype "input"))
      (node (ref "R8") (pin "1") (pinfunction "1_1") (pintype "input"))
    )
    (net (code "34") (name "Net-(LED9-C)") (class "Default")
      (node (ref "LED9") (pin "1") (pinfunction "C_1") (pintype "input"))
      (node (ref "R9") (pin "1") (pinfunction "1_1") (pintype "input"))
    )
    (net (code "35") (name "Net-(LED10-C)") (class "Default")
      (node (ref "LED10") (pin "1") (pinfunction "C_1") (pintype "input"))
      (node (ref "R10") (pin "1") (pinfunction "1_1") (pintype "input"))
    )
    (net (code "36") (name "Net-(LED11-C)") (class "Default")
      (node (ref "LED11") (pin "1") (pinfunction "C_1") (pintype "input"))
      (node (ref "R11") (pin "1") (pinfunction "1_1") (pintype "input"))
    )
    (net (code "37") (name "Net-(LED12-C)") (class "Default")
      (node (ref "LED12") (pin "1") (pinfunction "C_1") (pintype "input"))
      (node (ref "R12") (pin "1") (pinfunction "1_1") (pintype "input"))
    )
    (net (code "38") (name "Net-(LED13-C)") (class "Default")
      (node (ref "LED13") (pin "1") (pinfunction "C_1") (pintype "input"))
      (node (ref "R13") (pin "1") (pinfunction "1_1") (pintype "input"))
    )
    (net (code "39") (name "Net-(LED14-C)") (class "Default")
      (node (ref "LED14") (pin "1") (pinfunction "C_1") (pintype "input"))
      (node (ref "R14") (pin "1") (pinfunction "1_1") (pintype "input"))
    )
    (net (code "40") (name "Net-(LED15-C)") (class "Default")
      (node (ref "LED15") (pin "1") (pinfunction "C_1") (pintype "input"))
      (node (ref "R15") (pin "1") (pinfunction "1_1") (pintype "input"))
    )
    (net (code "41") (name "Net-(LED16-C)") (class "Default")
      (node (ref "LED16") (pin "1") (pinfunction "C_1") (pintype "input"))
      (node (ref "R16") (pin "1") (pinfunction "1_1") (pintype "input"))
    )
    (net (code "42") (name "unconnected-(CN1-Pad3)") (class "Default")
      (node (ref "CN1") (pin "3") (pinfunction "3_3") (pintype "unspecified+no_connect"))
    )
    (net (code "43") (name "unconnected-(CN1-Pad4)") (class "Default")
      (node (ref "CN1") (pin "4") (pinfunction "4_4") (pintype "unspecified+no_connect"))
    )
    (net (code "44") (name "unconnected-(USB1-EH-Pad25)") (class "Default")
      (node (ref "USB1") (pin "25") (pinfunction "EH_25") (pintype "unspecified+no_connect"))
    )
    (net (code "45") (name "unconnected-(USB2-EH-Pad25)") (class "Default")
      (node (ref "USB2") (pin "25") (pinfunction "EH_25") (pintype "unspecified+no_connect"))
    )
    (net (code "46") (name "unconnected-(USB3-EH-Pad25)") (class "Default")
      (node (ref "USB3") (pin "25") (pinfunction "EH_25") (pintype "unspecified+no_connect"))
    )
    (net (code "47") (name "unconnected-(USB4-EH-Pad25)") (class "Default")
      (node (ref "USB4") (pin "25") (pinfunction "EH_25") (pintype "unspecified+no_connect"))
    )
    (net (code "48") (name "unconnected-(USB5-EH-Pad25)") (class "Default")
      (node (ref "USB5") (pin "25") (pinfunction "EH_25") (pintype "unspecified+no_connect"))
    )
    (net (code "49") (name "unconnected-(USB6-EH-Pad25)") (class "Default")
      (node (ref "USB6") (pin "25") (pinfunction "EH_25") (pintype "unspecified+no_connect"))
    )
    (net (code "50") (name "unconnected-(USB7-EH-Pad25)") (class "Default")
      (node (ref "USB7") (pin "25") (pinfunction "EH_25") (pintype "unspecified+no_connect"))
    )
    (net (code "51") (name "unconnected-(USB8-EH-Pad25)") (class "Default")
      (node (ref "USB8") (pin "25") (pinfunction "EH_25") (pintype "unspecified+no_connect"))
    )
    (net (code "52") (name "unconnected-(USB9-EH-Pad25)") (class "Default")
      (node (ref "USB9") (pin "25") (pinfunction "EH_25") (pintype "unspecified+no_connect"))
    )
    (net (code "53") (name "unconnected-(USB10-EH-Pad25)") (class "Default")
      (node (ref "USB10") (pin "25") (pinfunction "EH_25") (pintype "unspecified+no_connect"))
    )
    (net (code "54") (name "unconnected-(USB11-EH-Pad25)") (class "Default")
      (node (ref "USB11") (pin "25") (pinfunction "EH_25") (pintype "unspecified+no_connect"))
    )
    (net (code "55") (name "unconnected-(USB12-EH-Pad25)") (class "Default")
      (node (ref "USB12") (pin "25") (pinfunction "EH_25") (pintype "unspecified+no_connect"))
    )
    (net (code "56") (name "unconnected-(USB13-EH-Pad25)") (class "Default")
      (node (ref "USB13") (pin "25") (pinfunction "EH_25") (pintype "unspecified+no_connect"))
    )
    (net (code "57") (name "unconnected-(USB14-EH-Pad25)") (class "Default")
      (node (ref "USB14") (pin "25") (pinfunction "EH_25") (pintype "unspecified+no_connect"))
    )
    (net (code "58") (name "unconnected-(USB15-EH-Pad25)") (class "Default")
      (node (ref "USB15") (pin "25") (pinfunction "EH_25") (pintype "unspecified+no_connect"))
    )
    (net (code "59") (name "unconnected-(USB16-EH-Pad25)") (class "Default")
      (node (ref "USB16") (pin "25") (pinfunction "EH_25") (pintype "unspecified+no_connect"))
    )
  )
)
